# ASARUM-S300CO2toGROVE.net
KiCad netlist of a schematic drawn in EAGLE
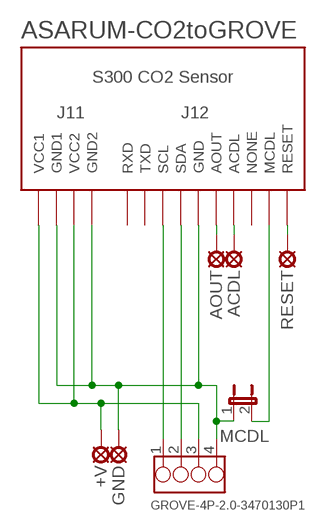
[diagram p0: schematic, sheet 1]

(export (version "E")
  (design (tool "Eeschema 10.0.6"))
  (components
    (comp (ref "+V")
      (value "LSP10")
      (footprint "eagle-import:LSP10")
      (libsource (lib "eagle-import") (part "LSP10"))
    )
    (comp (ref "ACDL")
      (value "LSP10")
      (footprint "eagle-import:LSP10")
      (libsource (lib "eagle-import") (part "LSP10"))
    )
    (comp (ref "AOUT")
      (value "LSP10")
      (footprint "eagle-import:LSP10")
      (libsource (lib "eagle-import") (part "LSP10"))
    )
    (comp (ref "GND")
      (value "LSP10")
      (footprint "eagle-import:LSP10")
      (libsource (lib "eagle-import") (part "LSP10"))
    )
    (comp (ref "GROVE_I2C")
      (value "GROVE-4P-2.0-3470130P1")
      (footprint "eagle-import:4P-2.0")
      (libsource (lib "eagle-import") (part "GROVE-4P-2.0-3470130P1"))
    )
    (comp (ref "MCDL")
      (value "JP1E")
      (footprint "eagle-import:JP1")
      (libsource (lib "eagle-import") (part "JP1E"))
    )
    (comp (ref "RESET")
      (value "LSP10")
      (footprint "eagle-import:LSP10")
      (libsource (lib "eagle-import") (part "LSP10"))
    )
    (comp (ref "S300")
      (value "S300")
      (footprint "eagle-import:S300REV")
      (libsource (lib "eagle-import") (part "S300"))
    )
  )
  (nets
    (net (code "1") (name "Net-(S300-ACDL)") (class "Default")
      (node (ref "ACDL") (pin "MP") (pinfunction "MP_MP") (pintype "passive"))
      (node (ref "S300") (pin "J12P$7_ACDL") (pinfunction "ACDL_J12P$7_ACDL") (pintype "bidirectional"))
    )
    (net (code "2") (name "Net-(S300-AOUT)") (class "Default")
      (node (ref "AOUT") (pin "MP") (pinfunction "MP_MP") (pintype "passive"))
      (node (ref "S300") (pin "J12P$6_AOUT") (pinfunction "AOUT_J12P$6_AOUT") (pintype "bidirectional"))
    )
    (net (code "3") (name "Net-(S300-GND)") (class "Default")
      (node (ref "GND") (pin "MP") (pinfunction "MP_MP") (pintype "passive"))
      (node (ref "GROVE_I2C") (pin "4") (pinfunction "4_4") (pintype "bidirectional"))
      (node (ref "MCDL") (pin "1") (pinfunction "1_1") (pintype "passive"))
      (node (ref "S300") (pin "J11P$2_GND") (pinfunction "GND1_J11P$2_GND") (pintype "bidirectional"))
      (node (ref "S300") (pin "J11P$4_GND") (pinfunction "GND2_J11P$4_GND") (pintype "bidirectional"))
      (node (ref "S300") (pin "J12P$5_GND") (pinfunction "GND_J12P$5_GND") (pintype "bidirectional"))
    )
    (net (code "4") (name "Net-(S300-MCDL)") (class "Default")
      (node (ref "MCDL") (pin "2") (pinfunction "2_2") (pintype "passive"))
      (node (ref "S300") (pin "J12P$9_MCDL") (pinfunction "MCDL_J12P$9_MCDL") (pintype "bidirectional"))
    )
    (net (code "5") (name "Net-(S300-RESET)") (class "Default")
      (node (ref "RESET") (pin "MP") (pinfunction "MP_MP") (pintype "passive"))
      (node (ref "S300") (pin "J12P$10_RESET") (pinfunction "RESET_J12P$10_RESET") (pintype "bidirectional"))
    )
    (net (code "6") (name "Net-(S300-SCL)") (class "Default")
      (node (ref "GROVE_I2C") (pin "1") (pinfunction "1_1") (pintype "bidirectional"))
      (node (ref "S300") (pin "J12P$3_SCL") (pinfunction "SCL_J12P$3_SCL") (pintype "bidirectional"))
    )
    (net (code "7") (name "Net-(S300-SDA)") (class "Default")
      (node (ref "GROVE_I2C") (pin "2") (pinfunction "2_2") (pintype "bidirectional"))
      (node (ref "S300") (pin "J12P$4_SDA") (pinfunction "SDA_J12P$4_SDA") (pintype "bidirectional"))
    )
    (net (code "8") (name "Net-(S300-VCC1)") (class "Default")
      (node (ref "+V") (pin "MP") (pinfunction "MP_MP") (pintype "passive"))
      (node (ref "GROVE_I2C") (pin "3") (pinfunction "3_3") (pintype "bidirectional"))
      (node (ref "S300") (pin "J11P$1_VCC") (pinfunction "VCC1_J11P$1_VCC") (pintype "bidirectional"))
      (node (ref "S300") (pin "J11P$3_VCC") (pinfunction "VCC2_J11P$3_VCC") (pintype "bidirectional"))
    )
    (net (code "9") (name "unconnected-(S300-NONE-PadJ12P$8_NONE)") (class "Default")
      (node (ref "S300") (pin "J12P$8_NONE") (pinfunction "NONE_J12P$8_NONE") (pintype "bidirectional"))
    )
    (net (code "10") (name "unconnected-(S300-RXD-PadJ12P$1_RXD)") (class "Default")
      (node (ref "S300") (pin "J12P$1_RXD") (pinfunction "RXD_J12P$1_RXD") (pintype "bidirectional"))
    )
    (net (code "11") (name "unconnected-(S300-TXD-PadJ12P$2_TXD)") (class "Default")
      (node (ref "S300") (pin "J12P$2_TXD") (pinfunction "TXD_J12P$2_TXD") (pintype "bidirectional"))
    )
  )
)
